# LED_Driver.net
KiCad netlist of a schematic drawn in Altium Designer
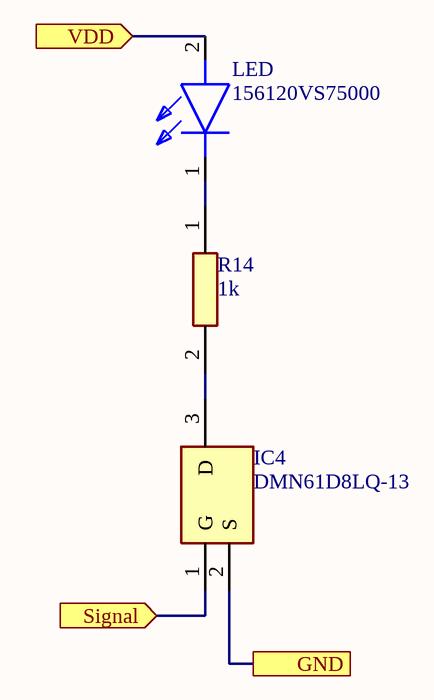
[diagram p0: LED_Driver.SchDoc]

(export (version "E")
  (design (tool "Eeschema 10.0.6"))
  (components
    (comp (ref "IC4")
      (value "DMN61D8LQ-13")
      (footprint "SamacSys:SOT96P240X110-3N")
      (description "Integrated Circuit")
      (fields (field (name "MOUSER PART NUMBER") "621-DMN61D8LQ-13"))
      (libsource (lib "SamacSys") (part "DMN61D8LQ-13"))
    )
    (comp (ref "LED")
      (value "156120VS75000")
      (footprint "SamacSys:156120VS75000")
      (description "LED")
      (fields (field (name "MOUSER PART NUMBER") "710-156120VS75000"))
      (libsource (lib "SamacSys") (part "156120VS75000"))
    )
    (comp (ref "R14")
      (value "1k")
      (footprint "SamacSys:RESC3116X65N")
      (description "Resistor")
      (fields
        (field (name "MANUFACTURER_PART_NUMBER") "CRGS1206J1K0")
        (field (name "MOUSER PART NUMBER") "279-CRGS1206J1K0")
      )
      (libsource (lib "*") (part "CRGS1206J1K0"))
    )
  )
  (nets
    (net (code "1") (name "/GND") (class "Default")
      (node (ref "IC4") (pin "2") (pinfunction "S_2") (pintype "passive"))
    )
    (net (code "2") (name "/Signal") (class "Default")
      (node (ref "IC4") (pin "1") (pinfunction "G_1") (pintype "passive"))
    )
    (net (code "3") (name "/VDD") (class "Default")
      (node (ref "LED") (pin "2") (pinfunction "A_2") (pintype "passive"))
    )
    (net (code "4") (name "Net-(IC4-D)") (class "Default")
      (node (ref "IC4") (pin "3") (pinfunction "D_3") (pintype "passive"))
      (node (ref "R14") (pin "2") (pinfunction "2_2") (pintype "passive"))
    )
    (net (code "5") (name "Net-(LED-K)") (class "Default")
      (node (ref "LED") (pin "1") (pinfunction "K_1") (pintype "passive"))
      (node (ref "R14") (pin "1") (pinfunction "1_1") (pintype "passive"))
    )
  )
)
